# Sheet1.net
KiCad netlist of a schematic drawn in Altium Designer
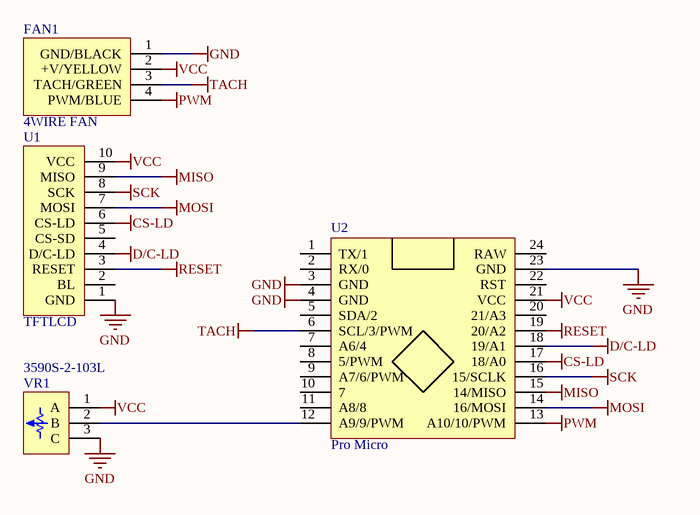
[diagram p0: Sheet1.SchDoc]

(export (version "E")
  (design (tool "Eeschema 10.0.6"))
  (components
    (comp (ref "FAN1")
      (value "4WIRE FAN")
      (footprint "WR-WTB 2,54mm 1X4")
      (libsource (lib "Schlib1") (part "4-WIRE_FAN"))
    )
    (comp (ref "U1") (value "TFTLCD") (footprint "TFTLCD") (libsource (lib "Schlib1") (part "TFTLCD")))
    (comp (ref "U2") (value "Pro Micro") (footprint "ProMicro") (libsource (lib "Schlib1") (part "ProMicro")))
    (comp (ref "VR1")
      (value "3590S-2-103L")
      (footprint "WR-WTB 2,54mm 1X3")
      (libsource (lib "Schlib1") (part "3590S-2-103L"))
    )
  )
  (nets
    (net (code "1") (name "CS-LD") (class "Default")
      (node (ref "U1") (pin "6") (pinfunction "CS-LD_6") (pintype "passive"))
      (node (ref "U2") (pin "17") (pinfunction "18/A0_17") (pintype "passive"))
    )
    (net (code "2") (name "D{slash}C-LD") (class "Default")
      (node (ref "U1") (pin "4") (pinfunction "D/C-LD_4") (pintype "passive"))
      (node (ref "U2") (pin "18") (pinfunction "19/A1_18") (pintype "passive"))
    )
    (net (code "3") (name "GND") (class "Default")
      (node (ref "FAN1") (pin "1") (pinfunction "GND/BLACK_1") (pintype "passive"))
      (node (ref "U1") (pin "1") (pinfunction "GND_1") (pintype "passive"))
      (node (ref "U2") (pin "23") (pinfunction "GND_23") (pintype "passive"))
      (node (ref "U2") (pin "3") (pinfunction "GND_3") (pintype "passive"))
      (node (ref "U2") (pin "4") (pinfunction "GND_4") (pintype "passive"))
      (node (ref "VR1") (pin "3") (pinfunction "C_3") (pintype "passive"))
    )
    (net (code "4") (name "MISO") (class "Default")
      (node (ref "U1") (pin "9") (pinfunction "MISO_9") (pintype "passive"))
      (node (ref "U2") (pin "15") (pinfunction "14/MISO_15") (pintype "passive"))
    )
    (net (code "5") (name "MOSI") (class "Default")
      (node (ref "U1") (pin "7") (pinfunction "MOSI_7") (pintype "passive"))
      (node (ref "U2") (pin "14") (pinfunction "16/MOSI_14") (pintype "passive"))
    )
    (net (code "6") (name "Net-(U2-A9{slash}9{slash}PWM)") (class "Default")
      (node (ref "U2") (pin "12") (pinfunction "A9/9/PWM_12") (pintype "passive"))
      (node (ref "VR1") (pin "2") (pinfunction "B_2") (pintype "passive"))
    )
    (net (code "7") (name "PWM") (class "Default")
      (node (ref "FAN1") (pin "4") (pinfunction "PWM/BLUE_4") (pintype "passive"))
      (node (ref "U2") (pin "13") (pinfunction "A10/10/PWM_13") (pintype "passive"))
    )
    (net (code "8") (name "RESET") (class "Default")
      (node (ref "U1") (pin "3") (pinfunction "RESET_3") (pintype "passive"))
      (node (ref "U2") (pin "19") (pinfunction "20/A2_19") (pintype "passive"))
    )
    (net (code "9") (name "SCK") (class "Default")
      (node (ref "U1") (pin "8") (pinfunction "SCK_8") (pintype "passive"))
      (node (ref "U2") (pin "16") (pinfunction "15/SCLK_16") (pintype "passive"))
    )
    (net (code "10") (name "TACH") (class "Default")
      (node (ref "FAN1") (pin "3") (pinfunction "TACH/GREEN_3") (pintype "passive"))
      (node (ref "U2") (pin "6") (pinfunction "SCL/3/PWM_6") (pintype "passive"))
    )
    (net (code "11") (name "VCC") (class "Default")
      (node (ref "FAN1") (pin "2") (pinfunction "+V/YELLOW_2") (pintype "passive"))
      (node (ref "U1") (pin "10") (pinfunction "VCC_10") (pintype "passive"))
      (node (ref "U2") (pin "21") (pinfunction "VCC_21") (pintype "passive"))
      (node (ref "VR1") (pin "1") (pinfunction "A_1") (pintype "passive"))
    )
    (net (code "12") (name "unconnected-(U1-BL-Pad2)") (class "Default")
      (node (ref "U1") (pin "2") (pinfunction "BL_2") (pintype "passive"))
    )
    (net (code "13") (name "unconnected-(U1-CS-SD-Pad5)") (class "Default")
      (node (ref "U1") (pin "5") (pinfunction "CS-SD_5") (pintype "passive"))
    )
    (net (code "14") (name "unconnected-(U2-5{slash}PWM-Pad8)") (class "Default")
      (node (ref "U2") (pin "8") (pinfunction "5/PWM_8") (pintype "passive"))
    )
    (net (code "15") (name "unconnected-(U2-7-Pad10)") (class "Default")
      (node (ref "U2") (pin "10") (pinfunction "7_10") (pintype "passive"))
    )
    (net (code "16") (name "unconnected-(U2-21{slash}A3-Pad20)") (class "Default")
      (node (ref "U2") (pin "20") (pinfunction "21/A3_20") (pintype "passive"))
    )
    (net (code "17") (name "unconnected-(U2-A6{slash}4-Pad7)") (class "Default")
      (node (ref "U2") (pin "7") (pinfunction "A6/4_7") (pintype "passive"))
    )
    (net (code "18") (name "unconnected-(U2-A7{slash}6{slash}PWM-Pad9)") (class "Default")
      (node (ref "U2") (pin "9") (pinfunction "A7/6/PWM_9") (pintype "passive"))
    )
    (net (code "19") (name "unconnected-(U2-A8{slash}8-Pad11)") (class "Default")
      (node (ref "U2") (pin "11") (pinfunction "A8/8_11") (pintype "passive"))
    )
    (net (code "20") (name "unconnected-(U2-RAW-Pad24)") (class "Default")
      (node (ref "U2") (pin "24") (pinfunction "RAW_24") (pintype "passive"))
    )
    (net (code "21") (name "unconnected-(U2-RST-Pad22)") (class "Default")
      (node (ref "U2") (pin "22") (pinfunction "RST_22") (pintype "passive"))
    )
    (net (code "22") (name "unconnected-(U2-RX{slash}0-Pad2)") (class "Default")
      (node (ref "U2") (pin "2") (pinfunction "RX/0_2") (pintype "passive"))
    )
    (net (code "23") (name "unconnected-(U2-SDA{slash}2-Pad5)") (class "Default")
      (node (ref "U2") (pin "5") (pinfunction "SDA/2_5") (pintype "passive"))
    )
    (net (code "24") (name "unconnected-(U2-TX{slash}1-Pad1)") (class "Default")
      (node (ref "U2") (pin "1") (pinfunction "TX/1_1") (pintype "passive"))
    )
  )
)
